# MLVDS_Transceivers.net
KiCad netlist of a schematic drawn in Altium Designer
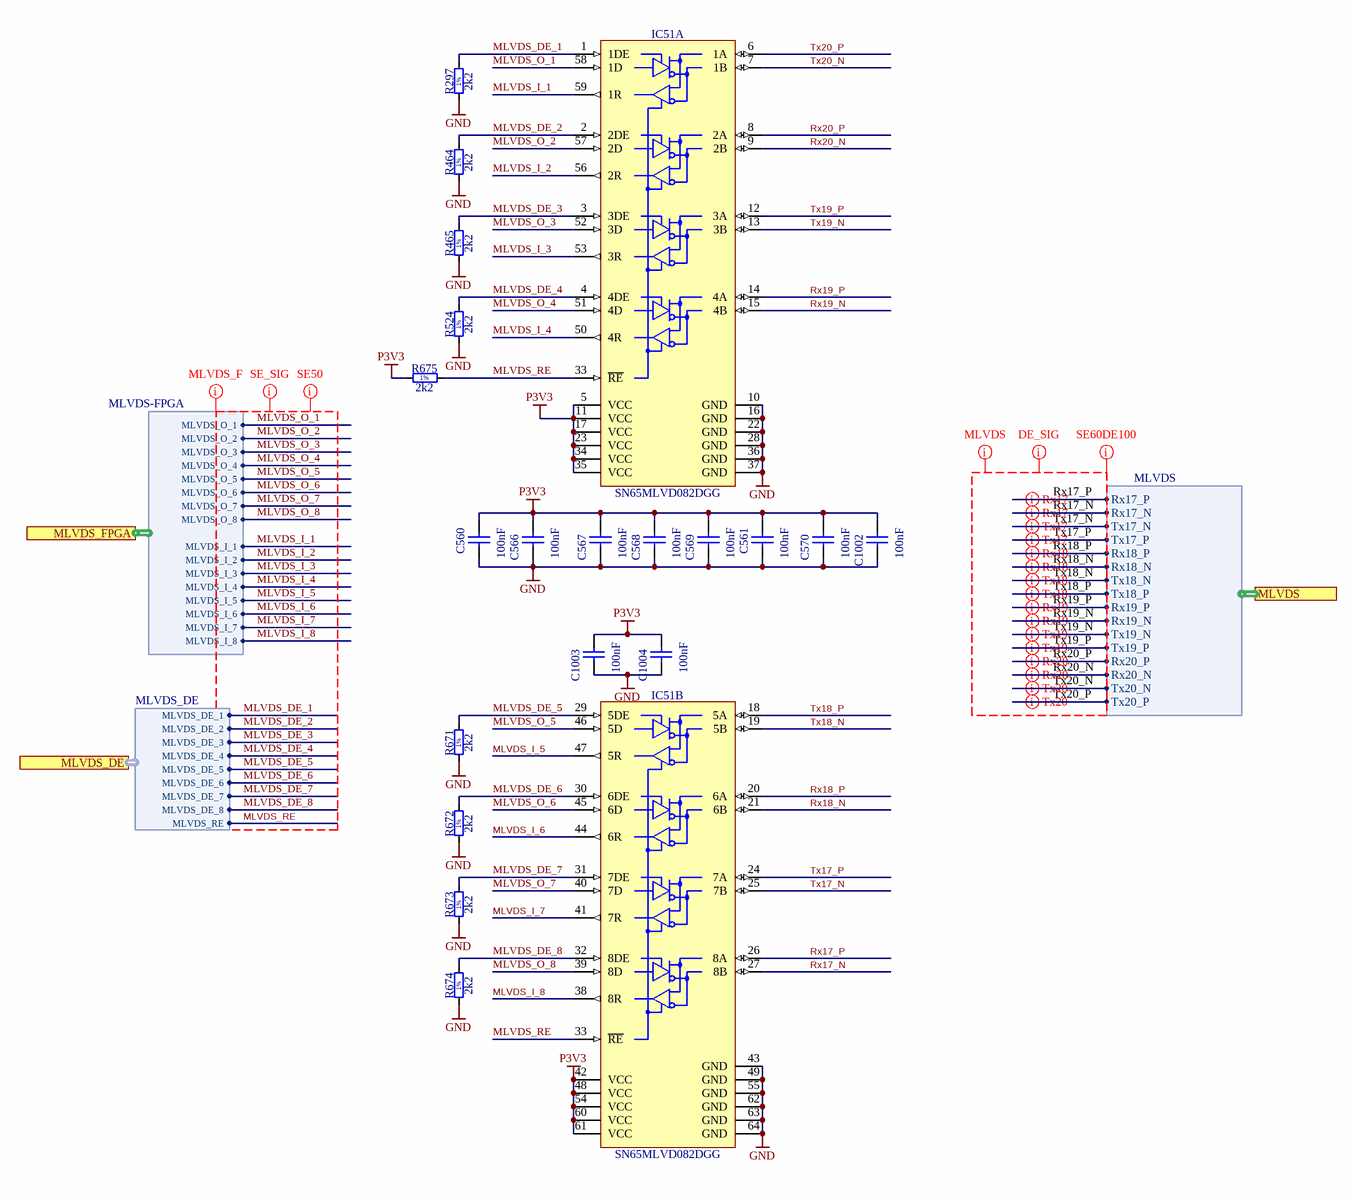
[diagram p0: MLVDS_Transceivers.SchDoc]

(export (version "E")
  (design (tool "Eeschema 10.0.6"))
  (components
    (comp (ref "C560")
      (value "100nF")
      (footprint "CAPC0603X33N")
      (description "Non-polarised capacitor")
      (fields
        (field (name "MANUFACTURER PART NUMBER") "CC0201_100NF_6.3V_10%_X5R")
        (field (name "MANUFACTURER") "GENERIC")
        (field (name "AUTHOR") "CERN DEM JLC")
      )
      (libsource (lib "Capacitors") (part "Capacitor - non polarized"))
    )
    (comp (ref "C561")
      (value "100nF")
      (footprint "CAPC0603X33N")
      (description "Non-polarised capacitor")
      (fields
        (field (name "MANUFACTURER PART NUMBER") "CC0201_100NF_6.3V_10%_X5R")
        (field (name "MANUFACTURER") "GENERIC")
        (field (name "AUTHOR") "CERN DEM JLC")
      )
      (libsource (lib "Capacitors") (part "Capacitor - non polarized"))
    )
    (comp (ref "C566")
      (value "100nF")
      (footprint "CAPC0603X33N")
      (description "Non-polarised capacitor")
      (fields
        (field (name "MANUFACTURER PART NUMBER") "CC0201_100NF_6.3V_10%_X5R")
        (field (name "MANUFACTURER") "GENERIC")
        (field (name "AUTHOR") "CERN DEM JLC")
      )
      (libsource (lib "Capacitors") (part "Capacitor - non polarized"))
    )
    (comp (ref "C567")
      (value "100nF")
      (footprint "CAPC0603X33N")
      (description "Non-polarised capacitor")
      (fields
        (field (name "MANUFACTURER PART NUMBER") "CC0201_100NF_6.3V_10%_X5R")
        (field (name "MANUFACTURER") "GENERIC")
        (field (name "AUTHOR") "CERN DEM JLC")
      )
      (libsource (lib "Capacitors") (part "Capacitor - non polarized"))
    )
    (comp (ref "C568")
      (value "100nF")
      (footprint "CAPC0603X33N")
      (description "Non-polarised capacitor")
      (fields
        (field (name "MANUFACTURER PART NUMBER") "CC0201_100NF_6.3V_10%_X5R")
        (field (name "MANUFACTURER") "GENERIC")
        (field (name "AUTHOR") "CERN DEM JLC")
      )
      (libsource (lib "Capacitors") (part "Capacitor - non polarized"))
    )
    (comp (ref "C569")
      (value "100nF")
      (footprint "CAPC0603X33N")
      (description "Non-polarised capacitor")
      (fields
        (field (name "MANUFACTURER PART NUMBER") "CC0201_100NF_6.3V_10%_X5R")
        (field (name "MANUFACTURER") "GENERIC")
        (field (name "AUTHOR") "CERN DEM JLC")
      )
      (libsource (lib "Capacitors") (part "Capacitor - non polarized"))
    )
    (comp (ref "C570")
      (value "100nF")
      (footprint "CAPC0603X33N")
      (description "Non-polarised capacitor")
      (fields
        (field (name "MANUFACTURER PART NUMBER") "CC0201_100NF_6.3V_10%_X5R")
        (field (name "MANUFACTURER") "GENERIC")
        (field (name "AUTHOR") "CERN DEM JLC")
      )
      (libsource (lib "Capacitors") (part "Capacitor - non polarized"))
    )
    (comp (ref "C1002")
      (value "100nF")
      (footprint "CAPC0603X33N")
      (description "Non-polarised capacitor")
      (fields
        (field (name "MANUFACTURER PART NUMBER") "CC0201_100NF_6.3V_10%_X5R")
        (field (name "MANUFACTURER") "GENERIC")
        (field (name "AUTHOR") "CERN DEM JLC")
      )
      (libsource (lib "Capacitors") (part "Capacitor - non polarized"))
    )
    (comp (ref "C1003")
      (value "100nF")
      (footprint "CAPC0603X33N")
      (description "Non-polarised capacitor")
      (fields
        (field (name "MANUFACTURER PART NUMBER") "CC0201_100NF_6.3V_10%_X5R")
        (field (name "MANUFACTURER") "GENERIC")
        (field (name "AUTHOR") "CERN DEM JLC")
      )
      (libsource (lib "Capacitors") (part "Capacitor - non polarized"))
    )
    (comp (ref "C1004")
      (value "100nF")
      (footprint "CAPC0603X33N")
      (description "Non-polarised capacitor")
      (fields
        (field (name "MANUFACTURER PART NUMBER") "CC0201_100NF_6.3V_10%_X5R")
        (field (name "MANUFACTURER") "GENERIC")
        (field (name "AUTHOR") "CERN DEM JLC")
      )
      (libsource (lib "Capacitors") (part "Capacitor - non polarized"))
    )
    (comp (ref "IC51")
      (value "SN65MLVD082DGG")
      (footprint "SOP50P810X120-64N")
      (description "8-Channel Half-Duplex M-LVDS Line Transceiver")
      (fields (field (name "MANUFACTURER") "TEXAS INSTRUMENTS") (field (name "AUTHOR") "CERN DEM BC"))
      (libsource (lib "ICs And Semiconductors") (part "SN65MLVD082"))
    )
    (comp (ref "R297")
      (value "2k2")
      (footprint "RESC1005X40N")
      (description "Resistor - 1%")
      (fields
        (field (name "PART NUMBER") "R0402_2K2_1%_0.0625W_100PPM")
        (field (name "POWER") "0.0625W")
        (field (name "AUTHOR") "CERN DEM JLC")
      )
      (libsource (lib "Resistors") (part "Resistor - 1%"))
    )
    (comp (ref "R464")
      (value "2k2")
      (footprint "RESC1005X40N")
      (description "Resistor - 1%")
      (fields
        (field (name "PART NUMBER") "R0402_2K2_1%_0.0625W_100PPM")
        (field (name "POWER") "0.0625W")
        (field (name "AUTHOR") "CERN DEM JLC")
      )
      (libsource (lib "Resistors") (part "Resistor - 1%"))
    )
    (comp (ref "R465")
      (value "2k2")
      (footprint "RESC1005X40N")
      (description "Resistor - 1%")
      (fields
        (field (name "PART NUMBER") "R0402_2K2_1%_0.0625W_100PPM")
        (field (name "POWER") "0.0625W")
        (field (name "AUTHOR") "CERN DEM JLC")
      )
      (libsource (lib "Resistors") (part "Resistor - 1%"))
    )
    (comp (ref "R524")
      (value "2k2")
      (footprint "RESC1005X40N")
      (description "Resistor - 1%")
      (fields
        (field (name "PART NUMBER") "R0402_2K2_1%_0.0625W_100PPM")
        (field (name "POWER") "0.0625W")
        (field (name "AUTHOR") "CERN DEM JLC")
      )
      (libsource (lib "Resistors") (part "Resistor - 1%"))
    )
    (comp (ref "R671")
      (value "2k2")
      (footprint "RESC1005X40N")
      (description "Resistor - 1%")
      (fields
        (field (name "PART NUMBER") "R0402_2K2_1%_0.0625W_100PPM")
        (field (name "POWER") "0.0625W")
        (field (name "AUTHOR") "CERN DEM JLC")
      )
      (libsource (lib "Resistors") (part "Resistor - 1%"))
    )
    (comp (ref "R672")
      (value "2k2")
      (footprint "RESC1005X40N")
      (description "Resistor - 1%")
      (fields
        (field (name "PART NUMBER") "R0402_2K2_1%_0.0625W_100PPM")
        (field (name "POWER") "0.0625W")
        (field (name "AUTHOR") "CERN DEM JLC")
      )
      (libsource (lib "Resistors") (part "Resistor - 1%"))
    )
    (comp (ref "R673")
      (value "2k2")
      (footprint "RESC1005X40N")
      (description "Resistor - 1%")
      (fields
        (field (name "PART NUMBER") "R0402_2K2_1%_0.0625W_100PPM")
        (field (name "POWER") "0.0625W")
        (field (name "AUTHOR") "CERN DEM JLC")
      )
      (libsource (lib "Resistors") (part "Resistor - 1%"))
    )
    (comp (ref "R674")
      (value "2k2")
      (footprint "RESC1005X40N")
      (description "Resistor - 1%")
      (fields
        (field (name "PART NUMBER") "R0402_2K2_1%_0.0625W_100PPM")
        (field (name "POWER") "0.0625W")
        (field (name "AUTHOR") "CERN DEM JLC")
      )
      (libsource (lib "Resistors") (part "Resistor - 1%"))
    )
    (comp (ref "R675")
      (value "2k2")
      (footprint "RESC1005X40N")
      (description "Resistor - 1%")
      (fields
        (field (name "PART NUMBER") "R0402_2K2_1%_0.0625W_100PPM")
        (field (name "POWER") "0.0625W")
        (field (name "AUTHOR") "CERN DEM JLC")
      )
      (libsource (lib "Resistors") (part "Resistor - 1%"))
    )
  )
  (nets
    (net (code "4") (name "/MLVDS_DE_1") (class "Default")
      (node (ref "IC51") (pin "1") (pinfunction "1DE_1") (pintype "input"))
      (node (ref "R297") (pin "2") (pinfunction "2_2") (pintype "passive"))
    )
    (net (code "5") (name "/MLVDS_DE_2") (class "Default")
      (node (ref "IC51") (pin "2") (pinfunction "2DE_2") (pintype "input"))
      (node (ref "R464") (pin "2") (pinfunction "2_2") (pintype "passive"))
    )
    (net (code "6") (name "/MLVDS_DE_3") (class "Default")
      (node (ref "IC51") (pin "3") (pinfunction "3DE_3") (pintype "input"))
      (node (ref "R465") (pin "2") (pinfunction "2_2") (pintype "passive"))
    )
    (net (code "7") (name "/MLVDS_DE_4") (class "Default")
      (node (ref "IC51") (pin "4") (pinfunction "4DE_4") (pintype "input"))
      (node (ref "R524") (pin "2") (pinfunction "2_2") (pintype "passive"))
    )
    (net (code "8") (name "/MLVDS_DE_5") (class "Default")
      (node (ref "IC51") (pin "29") (pinfunction "5DE_29") (pintype "input"))
      (node (ref "R671") (pin "2") (pinfunction "2_2") (pintype "passive"))
    )
    (net (code "9") (name "/MLVDS_DE_6") (class "Default")
      (node (ref "IC51") (pin "30") (pinfunction "6DE_30") (pintype "input"))
      (node (ref "R672") (pin "2") (pinfunction "2_2") (pintype "passive"))
    )
    (net (code "10") (name "/MLVDS_DE_7") (class "Default")
      (node (ref "IC51") (pin "31") (pinfunction "7DE_31") (pintype "input"))
      (node (ref "R673") (pin "2") (pinfunction "2_2") (pintype "passive"))
    )
    (net (code "11") (name "/MLVDS_DE_8") (class "Default")
      (node (ref "IC51") (pin "32") (pinfunction "8DE_32") (pintype "input"))
      (node (ref "R674") (pin "2") (pinfunction "2_2") (pintype "passive"))
    )
    (net (code "12") (name "/MLVDS_I_1") (class "Default")
      (node (ref "IC51") (pin "59") (pinfunction "1R_59") (pintype "output"))
    )
    (net (code "13") (name "/MLVDS_I_2") (class "Default")
      (node (ref "IC51") (pin "56") (pinfunction "2R_56") (pintype "output"))
    )
    (net (code "14") (name "/MLVDS_I_3") (class "Default")
      (node (ref "IC51") (pin "53") (pinfunction "3R_53") (pintype "output"))
    )
    (net (code "15") (name "/MLVDS_I_4") (class "Default")
      (node (ref "IC51") (pin "50") (pinfunction "4R_50") (pintype "output"))
    )
    (net (code "16") (name "/MLVDS_I_5") (class "Default")
      (node (ref "IC51") (pin "47") (pinfunction "5R_47") (pintype "output"))
    )
    (net (code "17") (name "/MLVDS_I_6") (class "Default")
      (node (ref "IC51") (pin "44") (pinfunction "6R_44") (pintype "output"))
    )
    (net (code "18") (name "/MLVDS_I_7") (class "Default")
      (node (ref "IC51") (pin "41") (pinfunction "7R_41") (pintype "output"))
    )
    (net (code "19") (name "/MLVDS_I_8") (class "Default")
      (node (ref "IC51") (pin "38") (pinfunction "8R_38") (pintype "output"))
    )
    (net (code "20") (name "/MLVDS_O_1") (class "Default")
      (node (ref "IC51") (pin "58") (pinfunction "1D_58") (pintype "input"))
    )
    (net (code "21") (name "/MLVDS_O_2") (class "Default")
      (node (ref "IC51") (pin "57") (pinfunction "2D_57") (pintype "input"))
    )
    (net (code "22") (name "/MLVDS_O_3") (class "Default")
      (node (ref "IC51") (pin "52") (pinfunction "3D_52") (pintype "input"))
    )
    (net (code "23") (name "/MLVDS_O_4") (class "Default")
      (node (ref "IC51") (pin "51") (pinfunction "4D_51") (pintype "input"))
    )
    (net (code "24") (name "/MLVDS_O_5") (class "Default")
      (node (ref "IC51") (pin "46") (pinfunction "5D_46") (pintype "input"))
    )
    (net (code "25") (name "/MLVDS_O_6") (class "Default")
      (node (ref "IC51") (pin "45") (pinfunction "6D_45") (pintype "input"))
    )
    (net (code "26") (name "/MLVDS_O_7") (class "Default")
      (node (ref "IC51") (pin "40") (pinfunction "7D_40") (pintype "input"))
    )
    (net (code "27") (name "/MLVDS_O_8") (class "Default")
      (node (ref "IC51") (pin "39") (pinfunction "8D_39") (pintype "input"))
    )
    (net (code "28") (name "/MLVDS_RE") (class "Default")
      (node (ref "IC51") (pin "33") (pinfunction "~{RE}_33") (pintype "input"))
      (node (ref "R675") (pin "2") (pinfunction "2_2") (pintype "passive"))
    )
    (net (code "29") (name "/Rx17_N") (class "Default")
      (node (ref "IC51") (pin "27") (pinfunction "8B_27") (pintype "bidirectional"))
    )
    (net (code "30") (name "/Rx17_P") (class "Default")
      (node (ref "IC51") (pin "26") (pinfunction "8A_26") (pintype "bidirectional"))
    )
    (net (code "31") (name "/Rx18_N") (class "Default")
      (node (ref "IC51") (pin "21") (pinfunction "6B_21") (pintype "bidirectional"))
    )
    (net (code "32") (name "/Rx18_P") (class "Default")
      (node (ref "IC51") (pin "20") (pinfunction "6A_20") (pintype "bidirectional"))
    )
    (net (code "33") (name "/Rx19_N") (class "Default")
      (node (ref "IC51") (pin "15") (pinfunction "4B_15") (pintype "bidirectional"))
    )
    (net (code "34") (name "/Rx19_P") (class "Default")
      (node (ref "IC51") (pin "14") (pinfunction "4A_14") (pintype "bidirectional"))
    )
    (net (code "35") (name "/Rx20_N") (class "Default")
      (node (ref "IC51") (pin "9") (pinfunction "2B_9") (pintype "bidirectional"))
    )
    (net (code "36") (name "/Rx20_P") (class "Default")
      (node (ref "IC51") (pin "8") (pinfunction "2A_8") (pintype "bidirectional"))
    )
    (net (code "37") (name "/Tx17_N") (class "Default")
      (node (ref "IC51") (pin "25") (pinfunction "7B_25") (pintype "bidirectional"))
    )
    (net (code "38") (name "/Tx17_P") (class "Default")
      (node (ref "IC51") (pin "24") (pinfunction "7A_24") (pintype "bidirectional"))
    )
    (net (code "39") (name "/Tx18_N") (class "Default")
      (node (ref "IC51") (pin "19") (pinfunction "5B_19") (pintype "bidirectional"))
    )
    (net (code "40") (name "/Tx18_P") (class "Default")
      (node (ref "IC51") (pin "18") (pinfunction "5A_18") (pintype "bidirectional"))
    )
    (net (code "41") (name "/Tx19_N") (class "Default")
      (node (ref "IC51") (pin "13") (pinfunction "3B_13") (pintype "bidirectional"))
    )
    (net (code "42") (name "/Tx19_P") (class "Default")
      (node (ref "IC51") (pin "12") (pinfunction "3A_12") (pintype "bidirectional"))
    )
    (net (code "43") (name "/Tx20_N") (class "Default")
      (node (ref "IC51") (pin "7") (pinfunction "1B_7") (pintype "bidirectional"))
    )
    (net (code "44") (name "/Tx20_P") (class "Default")
      (node (ref "IC51") (pin "6") (pinfunction "1A_6") (pintype "bidirectional"))
    )
    (net (code "48") (name "GND") (class "Default")
      (node (ref "C1002") (pin "2") (pinfunction "2_2") (pintype "passive"))
      (node (ref "C1003") (pin "2") (pinfunction "2_2") (pintype "passive"))
      (node (ref "C1004") (pin "2") (pinfunction "2_2") (pintype "passive"))
      (node (ref "C560") (pin "2") (pinfunction "2_2") (pintype "passive"))
      (node (ref "C561") (pin "2") (pinfunction "2_2") (pintype "passive"))
      (node (ref "C566") (pin "2") (pinfunction "2_2") (pintype "passive"))
      (node (ref "C567") (pin "2") (pinfunction "2_2") (pintype "passive"))
      (node (ref "C568") (pin "2") (pinfunction "2_2") (pintype "passive"))
      (node (ref "C569") (pin "2") (pinfunction "2_2") (pintype "passive"))
      (node (ref "C570") (pin "2") (pinfunction "2_2") (pintype "passive"))
      (node (ref "IC51") (pin "10") (pinfunction "GND_10") (pintype "power_in"))
      (node (ref "IC51") (pin "16") (pinfunction "GND_16") (pintype "power_in"))
      (node (ref "IC51") (pin "22") (pinfunction "GND_22") (pintype "power_in"))
      (node (ref "IC51") (pin "28") (pinfunction "GND_28") (pintype "power_in"))
      (node (ref "IC51") (pin "36") (pinfunction "GND_36") (pintype "power_in"))
      (node (ref "IC51") (pin "37") (pinfunction "GND_37") (pintype "power_in"))
      (node (ref "IC51") (pin "43") (pinfunction "GND_43") (pintype "power_in"))
      (node (ref "IC51") (pin "49") (pinfunction "GND_49") (pintype "power_in"))
      (node (ref "IC51") (pin "55") (pinfunction "GND_55") (pintype "power_in"))
      (node (ref "IC51") (pin "62") (pinfunction "GND_62") (pintype "power_in"))
      (node (ref "IC51") (pin "63") (pinfunction "GND_63") (pintype "power_in"))
      (node (ref "IC51") (pin "64") (pinfunction "GND_64") (pintype "power_in"))
      (node (ref "R297") (pin "1") (pinfunction "1_1") (pintype "passive"))
      (node (ref "R464") (pin "1") (pinfunction "1_1") (pintype "passive"))
      (node (ref "R465") (pin "1") (pinfunction "1_1") (pintype "passive"))
      (node (ref "R524") (pin "1") (pinfunction "1_1") (pintype "passive"))
      (node (ref "R671") (pin "1") (pinfunction "1_1") (pintype "passive"))
      (node (ref "R672") (pin "1") (pinfunction "1_1") (pintype "passive"))
      (node (ref "R673") (pin "1") (pinfunction "1_1") (pintype "passive"))
      (node (ref "R674") (pin "1") (pinfunction "1_1") (pintype "passive"))
    )
    (net (code "49") (name "P3V3") (class "Default")
      (node (ref "C1002") (pin "1") (pinfunction "1_1") (pintype "passive"))
      (node (ref "C1003") (pin "1") (pinfunction "1_1") (pintype "passive"))
      (node (ref "C1004") (pin "1") (pinfunction "1_1") (pintype "passive"))
      (node (ref "C560") (pin "1") (pinfunction "1_1") (pintype "passive"))
      (node (ref "C561") (pin "1") (pinfunction "1_1") (pintype "passive"))
      (node (ref "C566") (pin "1") (pinfunction "1_1") (pintype "passive"))
      (node (ref "C567") (pin "1") (pinfunction "1_1") (pintype "passive"))
      (node (ref "C568") (pin "1") (pinfunction "1_1") (pintype "passive"))
      (node (ref "C569") (pin "1") (pinfunction "1_1") (pintype "passive"))
      (node (ref "C570") (pin "1") (pinfunction "1_1") (pintype "passive"))
      (node (ref "IC51") (pin "11") (pinfunction "VCC_11") (pintype "power_in"))
      (node (ref "IC51") (pin "17") (pinfunction "VCC_17") (pintype "power_in"))
      (node (ref "IC51") (pin "23") (pinfunction "VCC_23") (pintype "power_in"))
      (node (ref "IC51") (pin "34") (pinfunction "VCC_34") (pintype "power_in"))
      (node (ref "IC51") (pin "35") (pinfunction "VCC_35") (pintype "power_in"))
      (node (ref "IC51") (pin "42") (pinfunction "VCC_42") (pintype "power_in"))
      (node (ref "IC51") (pin "48") (pinfunction "VCC_48") (pintype "power_in"))
      (node (ref "IC51") (pin "5") (pinfunction "VCC_5") (pintype "power_in"))
      (node (ref "IC51") (pin "54") (pinfunction "VCC_54") (pintype "power_in"))
      (node (ref "IC51") (pin "60") (pinfunction "VCC_60") (pintype "power_in"))
      (node (ref "IC51") (pin "61") (pinfunction "VCC_61") (pintype "power_in"))
      (node (ref "R675") (pin "1") (pinfunction "1_1") (pintype "passive"))
    )
  )
)
